# sb-sonata-fpgapwr.net
KiCad netlist of a schematic drawn in Altium Designer
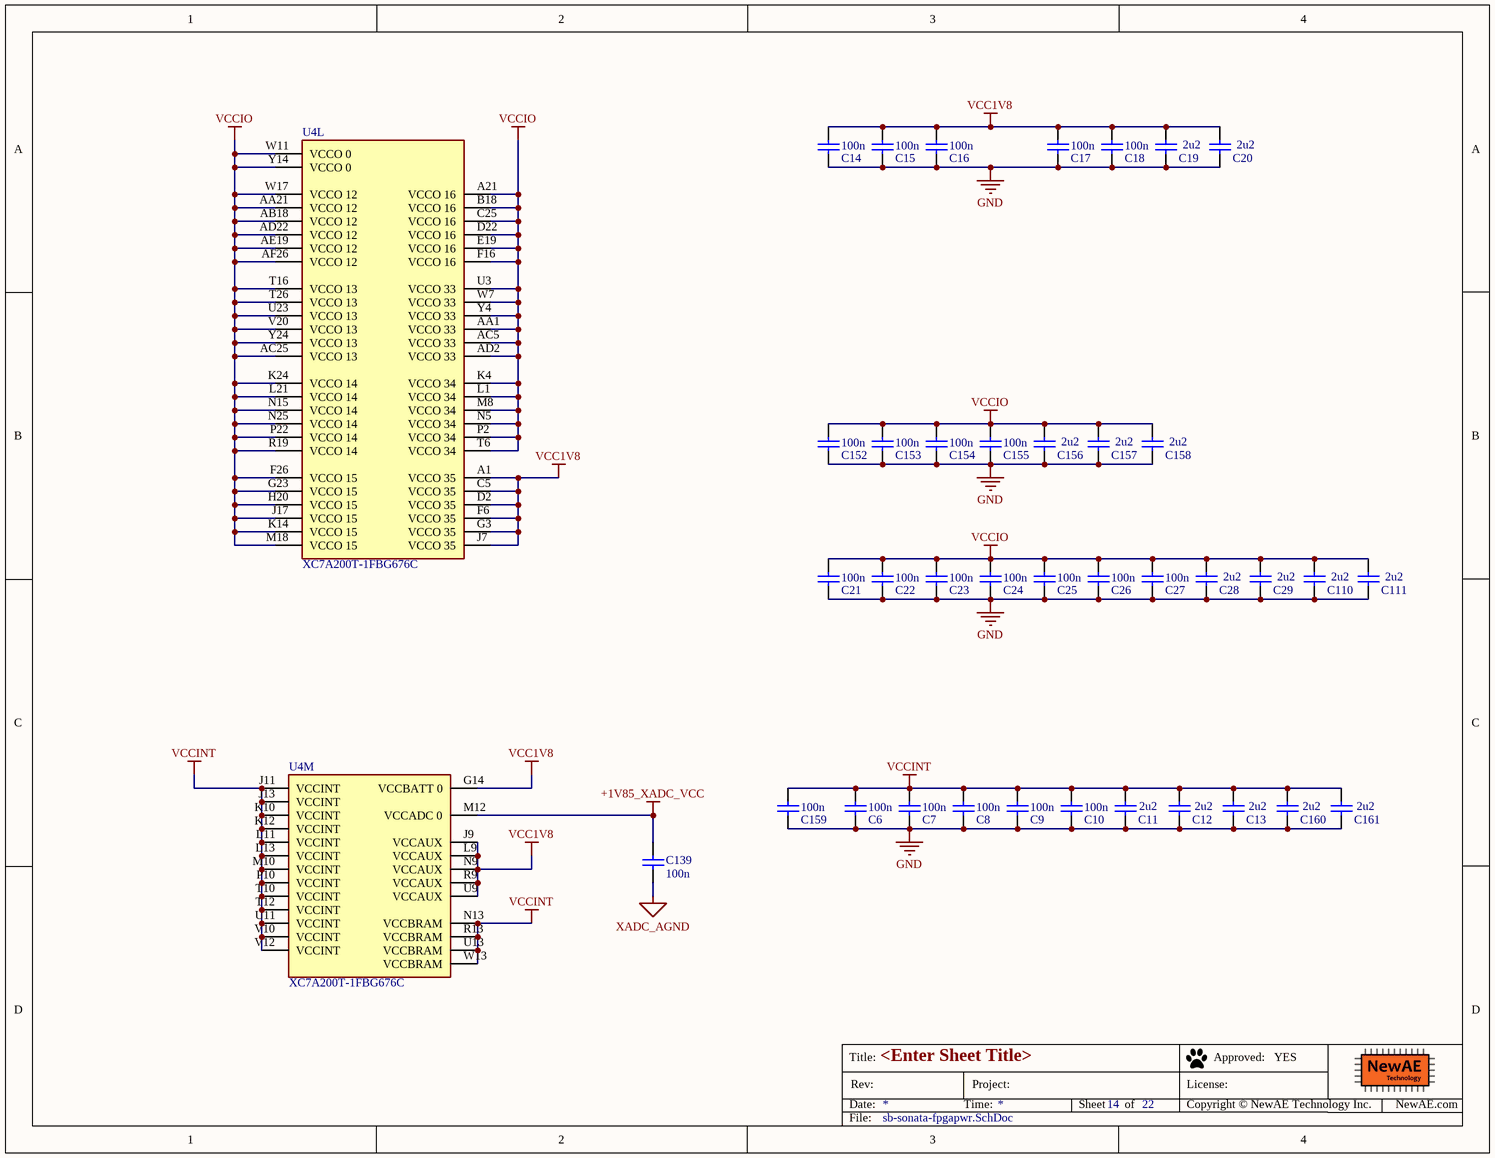
[diagram p0: sb-sonata-fpgapwr.SchDoc]

(export (version "E")
  (design (tool "Eeschema 10.0.6"))
  (components
    (comp (ref "C6")
      (value "100n")
      (footprint "CAPC0402_M")
      (description "100n, 0402")
      (fields (field (name "PART NUMBER") "CCHIP-100n-0402"))
      (libsource (lib "NewAE_AltiumLib") (part "CAP"))
    )
    (comp (ref "C7")
      (value "100n")
      (footprint "CAPC0402_M")
      (description "100n, 0402")
      (fields (field (name "PART NUMBER") "CCHIP-100n-0402"))
      (libsource (lib "NewAE_AltiumLib") (part "CAP"))
    )
    (comp (ref "C8")
      (value "100n")
      (footprint "CAPC0402_M")
      (description "100n, 0402")
      (fields (field (name "PART NUMBER") "CCHIP-100n-0402"))
      (libsource (lib "NewAE_AltiumLib") (part "CAP"))
    )
    (comp (ref "C9")
      (value "100n")
      (footprint "CAPC0402_M")
      (description "100n, 0402")
      (fields (field (name "PART NUMBER") "CCHIP-100n-0402"))
      (libsource (lib "NewAE_AltiumLib") (part "CAP"))
    )
    (comp (ref "C10")
      (value "100n")
      (footprint "CAPC0402_M")
      (description "100n, 0402")
      (fields (field (name "PART NUMBER") "CCHIP-100n-0402"))
      (libsource (lib "NewAE_AltiumLib") (part "CAP"))
    )
    (comp (ref "C11")
      (value "2u2")
      (footprint "CAPC0603_M")
      (description "2u2, 0603")
      (fields (field (name "PART NUMBER") "CCHIP-2u2-0603"))
      (libsource (lib "NewAE_AltiumLib") (part "CAP"))
    )
    (comp (ref "C12")
      (value "2u2")
      (footprint "CAPC0603_M")
      (description "2u2, 0603")
      (fields (field (name "PART NUMBER") "CCHIP-2u2-0603"))
      (libsource (lib "NewAE_AltiumLib") (part "CAP"))
    )
    (comp (ref "C13")
      (value "2u2")
      (footprint "CAPC0603_M")
      (description "2u2, 0603")
      (fields (field (name "PART NUMBER") "CCHIP-2u2-0603"))
      (libsource (lib "NewAE_AltiumLib") (part "CAP"))
    )
    (comp (ref "C14")
      (value "100n")
      (footprint "CAPC0402_M")
      (description "100n, 0402")
      (fields (field (name "PART NUMBER") "CCHIP-100n-0402"))
      (libsource (lib "NewAE_AltiumLib") (part "CAP"))
    )
    (comp (ref "C15")
      (value "100n")
      (footprint "CAPC0402_M")
      (description "100n, 0402")
      (fields (field (name "PART NUMBER") "CCHIP-100n-0402"))
      (libsource (lib "NewAE_AltiumLib") (part "CAP"))
    )
    (comp (ref "C16")
      (value "100n")
      (footprint "CAPC0402_M")
      (description "100n, 0402")
      (fields (field (name "PART NUMBER") "CCHIP-100n-0402"))
      (libsource (lib "NewAE_AltiumLib") (part "CAP"))
    )
    (comp (ref "C17")
      (value "100n")
      (footprint "CAPC0402_M")
      (description "100n, 0402")
      (fields (field (name "PART NUMBER") "CCHIP-100n-0402"))
      (libsource (lib "NewAE_AltiumLib") (part "CAP"))
    )
    (comp (ref "C18")
      (value "100n")
      (footprint "CAPC0402_M")
      (description "100n, 0402")
      (fields (field (name "PART NUMBER") "CCHIP-100n-0402"))
      (libsource (lib "NewAE_AltiumLib") (part "CAP"))
    )
    (comp (ref "C19")
      (value "2u2")
      (footprint "CAPC0603_M")
      (description "2u2, 0603")
      (fields (field (name "PART NUMBER") "CCHIP-2u2-0603"))
      (libsource (lib "NewAE_AltiumLib") (part "CAP"))
    )
    (comp (ref "C20")
      (value "2u2")
      (footprint "CAPC0603_M")
      (description "2u2, 0603")
      (fields (field (name "PART NUMBER") "CCHIP-2u2-0603"))
      (libsource (lib "NewAE_AltiumLib") (part "CAP"))
    )
    (comp (ref "C21")
      (value "100n")
      (footprint "CAPC0402_M")
      (description "100n, 0402")
      (fields (field (name "PART NUMBER") "CCHIP-100n-0402"))
      (libsource (lib "NewAE_AltiumLib") (part "CAP"))
    )
    (comp (ref "C22")
      (value "100n")
      (footprint "CAPC0402_M")
      (description "100n, 0402")
      (fields (field (name "PART NUMBER") "CCHIP-100n-0402"))
      (libsource (lib "NewAE_AltiumLib") (part "CAP"))
    )
    (comp (ref "C23")
      (value "100n")
      (footprint "CAPC0402_M")
      (description "100n, 0402")
      (fields (field (name "PART NUMBER") "CCHIP-100n-0402"))
      (libsource (lib "NewAE_AltiumLib") (part "CAP"))
    )
    (comp (ref "C24")
      (value "100n")
      (footprint "CAPC0402_M")
      (description "100n, 0402")
      (fields (field (name "PART NUMBER") "CCHIP-100n-0402"))
      (libsource (lib "NewAE_AltiumLib") (part "CAP"))
    )
    (comp (ref "C25")
      (value "100n")
      (footprint "CAPC0402_M")
      (description "100n, 0402")
      (fields (field (name "PART NUMBER") "CCHIP-100n-0402"))
      (libsource (lib "NewAE_AltiumLib") (part "CAP"))
    )
    (comp (ref "C26")
      (value "100n")
      (footprint "CAPC0402_M")
      (description "100n, 0402")
      (fields (field (name "PART NUMBER") "CCHIP-100n-0402"))
      (libsource (lib "NewAE_AltiumLib") (part "CAP"))
    )
    (comp (ref "C27")
      (value "100n")
      (footprint "CAPC0402_M")
      (description "100n, 0402")
      (fields (field (name "PART NUMBER") "CCHIP-100n-0402"))
      (libsource (lib "NewAE_AltiumLib") (part "CAP"))
    )
    (comp (ref "C28")
      (value "2u2")
      (footprint "CAPC0603_M")
      (description "2u2, 0603")
      (fields (field (name "PART NUMBER") "CCHIP-2u2-0603"))
      (libsource (lib "NewAE_AltiumLib") (part "CAP"))
    )
    (comp (ref "C29")
      (value "2u2")
      (footprint "CAPC0603_M")
      (description "2u2, 0603")
      (fields (field (name "PART NUMBER") "CCHIP-2u2-0603"))
      (libsource (lib "NewAE_AltiumLib") (part "CAP"))
    )
    (comp (ref "C110")
      (value "2u2")
      (footprint "CAPC0603_M")
      (description "2u2, 0603")
      (fields (field (name "PART NUMBER") "CCHIP-2u2-0603"))
      (libsource (lib "NewAE_AltiumLib") (part "CAP"))
    )
    (comp (ref "C111")
      (value "2u2")
      (footprint "CAPC0603_M")
      (description "2u2, 0603")
      (fields (field (name "PART NUMBER") "CCHIP-2u2-0603"))
      (libsource (lib "NewAE_AltiumLib") (part "CAP"))
    )
    (comp (ref "C139")
      (value "100n")
      (footprint "CAPC0402_M")
      (description "100n, 0402")
      (fields (field (name "PART NUMBER") "CCHIP-100n-0402"))
      (libsource (lib "NewAE_AltiumLib") (part "CAP"))
    )
    (comp (ref "C152")
      (value "100n")
      (footprint "CAPC0402_M")
      (description "100n, 0402")
      (fields (field (name "PART NUMBER") "CCHIP-100n-0402"))
      (libsource (lib "NewAE_AltiumLib") (part "CAP"))
    )
    (comp (ref "C153")
      (value "100n")
      (footprint "CAPC0402_M")
      (description "100n, 0402")
      (fields (field (name "PART NUMBER") "CCHIP-100n-0402"))
      (libsource (lib "NewAE_AltiumLib") (part "CAP"))
    )
    (comp (ref "C154")
      (value "100n")
      (footprint "CAPC0402_M")
      (description "100n, 0402")
      (fields (field (name "PART NUMBER") "CCHIP-100n-0402"))
      (libsource (lib "NewAE_AltiumLib") (part "CAP"))
    )
    (comp (ref "C155")
      (value "100n")
      (footprint "CAPC0402_M")
      (description "100n, 0402")
      (fields (field (name "PART NUMBER") "CCHIP-100n-0402"))
      (libsource (lib "NewAE_AltiumLib") (part "CAP"))
    )
    (comp (ref "C156")
      (value "2u2")
      (footprint "CAPC0603_M")
      (description "2u2, 0603")
      (fields (field (name "PART NUMBER") "CCHIP-2u2-0603"))
      (libsource (lib "NewAE_AltiumLib") (part "CAP"))
    )
    (comp (ref "C157")
      (value "2u2")
      (footprint "CAPC0603_M")
      (description "2u2, 0603")
      (fields (field (name "PART NUMBER") "CCHIP-2u2-0603"))
      (libsource (lib "NewAE_AltiumLib") (part "CAP"))
    )
    (comp (ref "C158")
      (value "2u2")
      (footprint "CAPC0603_M")
      (description "2u2, 0603")
      (fields (field (name "PART NUMBER") "CCHIP-2u2-0603"))
      (libsource (lib "NewAE_AltiumLib") (part "CAP"))
    )
    (comp (ref "C159")
      (value "100n")
      (footprint "CAPC0402_M")
      (description "100n, 0402")
      (fields (field (name "PART NUMBER") "CCHIP-100n-0402"))
      (libsource (lib "NewAE_AltiumLib") (part "CAP"))
    )
    (comp (ref "C160")
      (value "2u2")
      (footprint "CAPC0603_M")
      (description "2u2, 0603")
      (fields (field (name "PART NUMBER") "CCHIP-2u2-0603"))
      (libsource (lib "NewAE_AltiumLib") (part "CAP"))
    )
    (comp (ref "C161")
      (value "2u2")
      (footprint "CAPC0603_M")
      (description "2u2, 0603")
      (fields (field (name "PART NUMBER") "CCHIP-2u2-0603"))
      (libsource (lib "NewAE_AltiumLib") (part "CAP"))
    )
    (comp (ref "U4")
      (value "XC7A200T-1FBG676C")
      (footprint "FP-XC7A200T-1FBG676C-MFG")
      (description "IC FPGA 400 I/O 676FCBGA")
      (fields
        (field (name "OCTOPART") "https://octopart.com/xc7a200t-1fbg676c-xilinx-27810760")
        (field (name "MANUFACTURER") "Xilinx")
      )
      (libsource (lib "Altium Content Vault") (part "4b217bf1b8a92a9e4e40d14dbdee1ba"))
    )
  )
  (nets
    (net (code "1") (name "+1V85_XADC_VCC") (class "Default")
      (node (ref "C139") (pin "1") (pinfunction "1_1") (pintype "passive"))
      (node (ref "U4") (pin "M12") (pinfunction "VCCADC_0_M12") (pintype "power_in"))
    )
    (net (code "2") (name "GND") (class "Default")
      (node (ref "C10") (pin "2") (pinfunction "2_2") (pintype "passive"))
      (node (ref "C11") (pin "2") (pinfunction "2_2") (pintype "passive"))
      (node (ref "C110") (pin "2") (pinfunction "2_2") (pintype "passive"))
      (node (ref "C111") (pin "2") (pinfunction "2_2") (pintype "passive"))
      (node (ref "C12") (pin "2") (pinfunction "2_2") (pintype "passive"))
      (node (ref "C13") (pin "2") (pinfunction "2_2") (pintype "passive"))
      (node (ref "C14") (pin "2") (pinfunction "2_2") (pintype "passive"))
      (node (ref "C15") (pin "2") (pinfunction "2_2") (pintype "passive"))
      (node (ref "C152") (pin "2") (pinfunction "2_2") (pintype "passive"))
      (node (ref "C153") (pin "2") (pinfunction "2_2") (pintype "passive"))
      (node (ref "C154") (pin "2") (pinfunction "2_2") (pintype "passive"))
      (node (ref "C155") (pin "2") (pinfunction "2_2") (pintype "passive"))
      (node (ref "C156") (pin "2") (pinfunction "2_2") (pintype "passive"))
      (node (ref "C157") (pin "2") (pinfunction "2_2") (pintype "passive"))
      (node (ref "C158") (pin "2") (pinfunction "2_2") (pintype "passive"))
      (node (ref "C159") (pin "2") (pinfunction "2_2") (pintype "passive"))
      (node (ref "C16") (pin "2") (pinfunction "2_2") (pintype "passive"))
      (node (ref "C160") (pin "2") (pinfunction "2_2") (pintype "passive"))
      (node (ref "C161") (pin "2") (pinfunction "2_2") (pintype "passive"))
      (node (ref "C17") (pin "2") (pinfunction "2_2") (pintype "passive"))
      (node (ref "C18") (pin "2") (pinfunction "2_2") (pintype "passive"))
      (node (ref "C19") (pin "2") (pinfunction "2_2") (pintype "passive"))
      (node (ref "C20") (pin "2") (pinfunction "2_2") (pintype "passive"))
      (node (ref "C21") (pin "2") (pinfunction "2_2") (pintype "passive"))
      (node (ref "C22") (pin "2") (pinfunction "2_2") (pintype "passive"))
      (node (ref "C23") (pin "2") (pinfunction "2_2") (pintype "passive"))
      (node (ref "C24") (pin "2") (pinfunction "2_2") (pintype "passive"))
      (node (ref "C25") (pin "2") (pinfunction "2_2") (pintype "passive"))
      (node (ref "C26") (pin "2") (pinfunction "2_2") (pintype "passive"))
      (node (ref "C27") (pin "2") (pinfunction "2_2") (pintype "passive"))
      (node (ref "C28") (pin "2") (pinfunction "2_2") (pintype "passive"))
      (node (ref "C29") (pin "2") (pinfunction "2_2") (pintype "passive"))
      (node (ref "C6") (pin "2") (pinfunction "2_2") (pintype "passive"))
      (node (ref "C7") (pin "2") (pinfunction "2_2") (pintype "passive"))
      (node (ref "C8") (pin "2") (pinfunction "2_2") (pintype "passive"))
      (node (ref "C9") (pin "2") (pinfunction "2_2") (pintype "passive"))
    )
    (net (code "3") (name "VCC1V8") (class "Default")
      (node (ref "C14") (pin "1") (pinfunction "1_1") (pintype "passive"))
      (node (ref "C15") (pin "1") (pinfunction "1_1") (pintype "passive"))
      (node (ref "C16") (pin "1") (pinfunction "1_1") (pintype "passive"))
      (node (ref "C17") (pin "1") (pinfunction "1_1") (pintype "passive"))
      (node (ref "C18") (pin "1") (pinfunction "1_1") (pintype "passive"))
      (node (ref "C19") (pin "1") (pinfunction "1_1") (pintype "passive"))
      (node (ref "C20") (pin "1") (pinfunction "1_1") (pintype "passive"))
      (node (ref "U4") (pin "A1") (pinfunction "VCCO_35_A1") (pintype "power_in"))
      (node (ref "U4") (pin "C5") (pinfunction "VCCO_35_C5") (pintype "power_in"))
      (node (ref "U4") (pin "D2") (pinfunction "VCCO_35_D2") (pintype "power_in"))
      (node (ref "U4") (pin "F6") (pinfunction "VCCO_35_F6") (pintype "power_in"))
      (node (ref "U4") (pin "G14") (pinfunction "VCCBATT_0_G14") (pintype "power_in"))
      (node (ref "U4") (pin "G3") (pinfunction "VCCO_35_G3") (pintype "power_in"))
      (node (ref "U4") (pin "J7") (pinfunction "VCCO_35_J7") (pintype "power_in"))
      (node (ref "U4") (pin "J9") (pinfunction "VCCAUX_J9") (pintype "power_in"))
      (node (ref "U4") (pin "L9") (pinfunction "VCCAUX_L9") (pintype "power_in"))
      (node (ref "U4") (pin "N9") (pinfunction "VCCAUX_N9") (pintype "power_in"))
      (node (ref "U4") (pin "R9") (pinfunction "VCCAUX_R9") (pintype "power_in"))
      (node (ref "U4") (pin "U9") (pinfunction "VCCAUX_U9") (pintype "power_in"))
    )
    (net (code "4") (name "VCCINT") (class "Default")
      (node (ref "C10") (pin "1") (pinfunction "1_1") (pintype "passive"))
      (node (ref "C11") (pin "1") (pinfunction "1_1") (pintype "passive"))
      (node (ref "C12") (pin "1") (pinfunction "1_1") (pintype "passive"))
      (node (ref "C13") (pin "1") (pinfunction "1_1") (pintype "passive"))
      (node (ref "C159") (pin "1") (pinfunction "1_1") (pintype "passive"))
      (node (ref "C160") (pin "1") (pinfunction "1_1") (pintype "passive"))
      (node (ref "C161") (pin "1") (pinfunction "1_1") (pintype "passive"))
      (node (ref "C6") (pin "1") (pinfunction "1_1") (pintype "passive"))
      (node (ref "C7") (pin "1") (pinfunction "1_1") (pintype "passive"))
      (node (ref "C8") (pin "1") (pinfunction "1_1") (pintype "passive"))
      (node (ref "C9") (pin "1") (pinfunction "1_1") (pintype "passive"))
      (node (ref "U4") (pin "J11") (pinfunction "VCCINT_J11") (pintype "power_in"))
      (node (ref "U4") (pin "J13") (pinfunction "VCCINT_J13") (pintype "power_in"))
      (node (ref "U4") (pin "K10") (pinfunction "VCCINT_K10") (pintype "power_in"))
      (node (ref "U4") (pin "K12") (pinfunction "VCCINT_K12") (pintype "power_in"))
      (node (ref "U4") (pin "L11") (pinfunction "VCCINT_L11") (pintype "power_in"))
      (node (ref "U4") (pin "L13") (pinfunction "VCCINT_L13") (pintype "power_in"))
      (node (ref "U4") (pin "M10") (pinfunction "VCCINT_M10") (pintype "power_in"))
      (node (ref "U4") (pin "N13") (pinfunction "VCCBRAM_N13") (pintype "power_in"))
      (node (ref "U4") (pin "P10") (pinfunction "VCCINT_P10") (pintype "power_in"))
      (node (ref "U4") (pin "R13") (pinfunction "VCCBRAM_R13") (pintype "power_in"))
      (node (ref "U4") (pin "T10") (pinfunction "VCCINT_T10") (pintype "power_in"))
      (node (ref "U4") (pin "T12") (pinfunction "VCCINT_T12") (pintype "power_in"))
      (node (ref "U4") (pin "U11") (pinfunction "VCCINT_U11") (pintype "power_in"))
      (node (ref "U4") (pin "U13") (pinfunction "VCCBRAM_U13") (pintype "power_in"))
      (node (ref "U4") (pin "V10") (pinfunction "VCCINT_V10") (pintype "power_in"))
      (node (ref "U4") (pin "V12") (pinfunction "VCCINT_V12") (pintype "power_in"))
      (node (ref "U4") (pin "W13") (pinfunction "VCCBRAM_W13") (pintype "power_in"))
    )
    (net (code "5") (name "VCCIO") (class "Default")
      (node (ref "C110") (pin "1") (pinfunction "1_1") (pintype "passive"))
      (node (ref "C111") (pin "1") (pinfunction "1_1") (pintype "passive"))
      (node (ref "C152") (pin "1") (pinfunction "1_1") (pintype "passive"))
      (node (ref "C153") (pin "1") (pinfunction "1_1") (pintype "passive"))
      (node (ref "C154") (pin "1") (pinfunction "1_1") (pintype "passive"))
      (node (ref "C155") (pin "1") (pinfunction "1_1") (pintype "passive"))
      (node (ref "C156") (pin "1") (pinfunction "1_1") (pintype "passive"))
      (node (ref "C157") (pin "1") (pinfunction "1_1") (pintype "passive"))
      (node (ref "C158") (pin "1") (pinfunction "1_1") (pintype "passive"))
      (node (ref "C21") (pin "1") (pinfunction "1_1") (pintype "passive"))
      (node (ref "C22") (pin "1") (pinfunction "1_1") (pintype "passive"))
      (node (ref "C23") (pin "1") (pinfunction "1_1") (pintype "passive"))
      (node (ref "C24") (pin "1") (pinfunction "1_1") (pintype "passive"))
      (node (ref "C25") (pin "1") (pinfunction "1_1") (pintype "passive"))
      (node (ref "C26") (pin "1") (pinfunction "1_1") (pintype "passive"))
      (node (ref "C27") (pin "1") (pinfunction "1_1") (pintype "passive"))
      (node (ref "C28") (pin "1") (pinfunction "1_1") (pintype "passive"))
      (node (ref "C29") (pin "1") (pinfunction "1_1") (pintype "passive"))
      (node (ref "U4") (pin "A21") (pinfunction "VCCO_16_A21") (pintype "power_in"))
      (node (ref "U4") (pin "AA1") (pinfunction "VCCO_33_AA1") (pintype "power_in"))
      (node (ref "U4") (pin "AA21") (pinfunction "VCCO_12_AA21") (pintype "power_in"))
      (node (ref "U4") (pin "AB18") (pinfunction "VCCO_12_AB18") (pintype "power_in"))
      (node (ref "U4") (pin "AC25") (pinfunction "VCCO_13_AC25") (pintype "power_in"))
      (node (ref "U4") (pin "AC5") (pinfunction "VCCO_33_AC5") (pintype "power_in"))
      (node (ref "U4") (pin "AD2") (pinfunction "VCCO_33_AD2") (pintype "power_in"))
      (node (ref "U4") (pin "AD22") (pinfunction "VCCO_12_AD22") (pintype "power_in"))
      (node (ref "U4") (pin "AE19") (pinfunction "VCCO_12_AE19") (pintype "power_in"))
      (node (ref "U4") (pin "AF26") (pinfunction "VCCO_12_AF26") (pintype "power_in"))
      (node (ref "U4") (pin "B18") (pinfunction "VCCO_16_B18") (pintype "power_in"))
      (node (ref "U4") (pin "C25") (pinfunction "VCCO_16_C25") (pintype "power_in"))
      (node (ref "U4") (pin "D22") (pinfunction "VCCO_16_D22") (pintype "power_in"))
      (node (ref "U4") (pin "E19") (pinfunction "VCCO_16_E19") (pintype "power_in"))
      (node (ref "U4") (pin "F16") (pinfunction "VCCO_16_F16") (pintype "power_in"))
      (node (ref "U4") (pin "F26") (pinfunction "VCCO_15_F26") (pintype "power_in"))
      (node (ref "U4") (pin "G23") (pinfunction "VCCO_15_G23") (pintype "power_in"))
      (node (ref "U4") (pin "H20") (pinfunction "VCCO_15_H20") (pintype "power_in"))
      (node (ref "U4") (pin "J17") (pinfunction "VCCO_15_J17") (pintype "power_in"))
      (node (ref "U4") (pin "K14") (pinfunction "VCCO_15_K14") (pintype "power_in"))
      (node (ref "U4") (pin "K24") (pinfunction "VCCO_14_K24") (pintype "power_in"))
      (node (ref "U4") (pin "K4") (pinfunction "VCCO_34_K4") (pintype "power_in"))
      (node (ref "U4") (pin "L1") (pinfunction "VCCO_34_L1") (pintype "power_in"))
      (node (ref "U4") (pin "L21") (pinfunction "VCCO_14_L21") (pintype "power_in"))
      (node (ref "U4") (pin "M18") (pinfunction "VCCO_15_M18") (pintype "power_in"))
      (node (ref "U4") (pin "M8") (pinfunction "VCCO_34_M8") (pintype "power_in"))
      (node (ref "U4") (pin "N15") (pinfunction "VCCO_14_N15") (pintype "power_in"))
      (node (ref "U4") (pin "N25") (pinfunction "VCCO_14_N25") (pintype "power_in"))
      (node (ref "U4") (pin "N5") (pinfunction "VCCO_34_N5") (pintype "power_in"))
      (node (ref "U4") (pin "P2") (pinfunction "VCCO_34_P2") (pintype "power_in"))
      (node (ref "U4") (pin "P22") (pinfunction "VCCO_14_P22") (pintype "power_in"))
      (node (ref "U4") (pin "R19") (pinfunction "VCCO_14_R19") (pintype "power_in"))
      (node (ref "U4") (pin "T16") (pinfunction "VCCO_13_T16") (pintype "power_in"))
      (node (ref "U4") (pin "T26") (pinfunction "VCCO_13_T26") (pintype "power_in"))
      (node (ref "U4") (pin "T6") (pinfunction "VCCO_34_T6") (pintype "power_in"))
      (node (ref "U4") (pin "U23") (pinfunction "VCCO_13_U23") (pintype "power_in"))
      (node (ref "U4") (pin "U3") (pinfunction "VCCO_33_U3") (pintype "power_in"))
      (node (ref "U4") (pin "V20") (pinfunction "VCCO_13_V20") (pintype "power_in"))
      (node (ref "U4") (pin "W11") (pinfunction "VCCO_0_W11") (pintype "power_in"))
      (node (ref "U4") (pin "W17") (pinfunction "VCCO_12_W17") (pintype "power_in"))
      (node (ref "U4") (pin "W7") (pinfunction "VCCO_33_W7") (pintype "power_in"))
      (node (ref "U4") (pin "Y14") (pinfunction "VCCO_0_Y14") (pintype "power_in"))
      (node (ref "U4") (pin "Y24") (pinfunction "VCCO_13_Y24") (pintype "power_in"))
      (node (ref "U4") (pin "Y4") (pinfunction "VCCO_33_Y4") (pintype "power_in"))
    )
    (net (code "6") (name "XADC_AGND") (class "Default")
      (node (ref "C139") (pin "2") (pinfunction "2_2") (pintype "passive"))
    )
  )
)
